# main_02.net
KiCad netlist of a schematic drawn in EAGLE
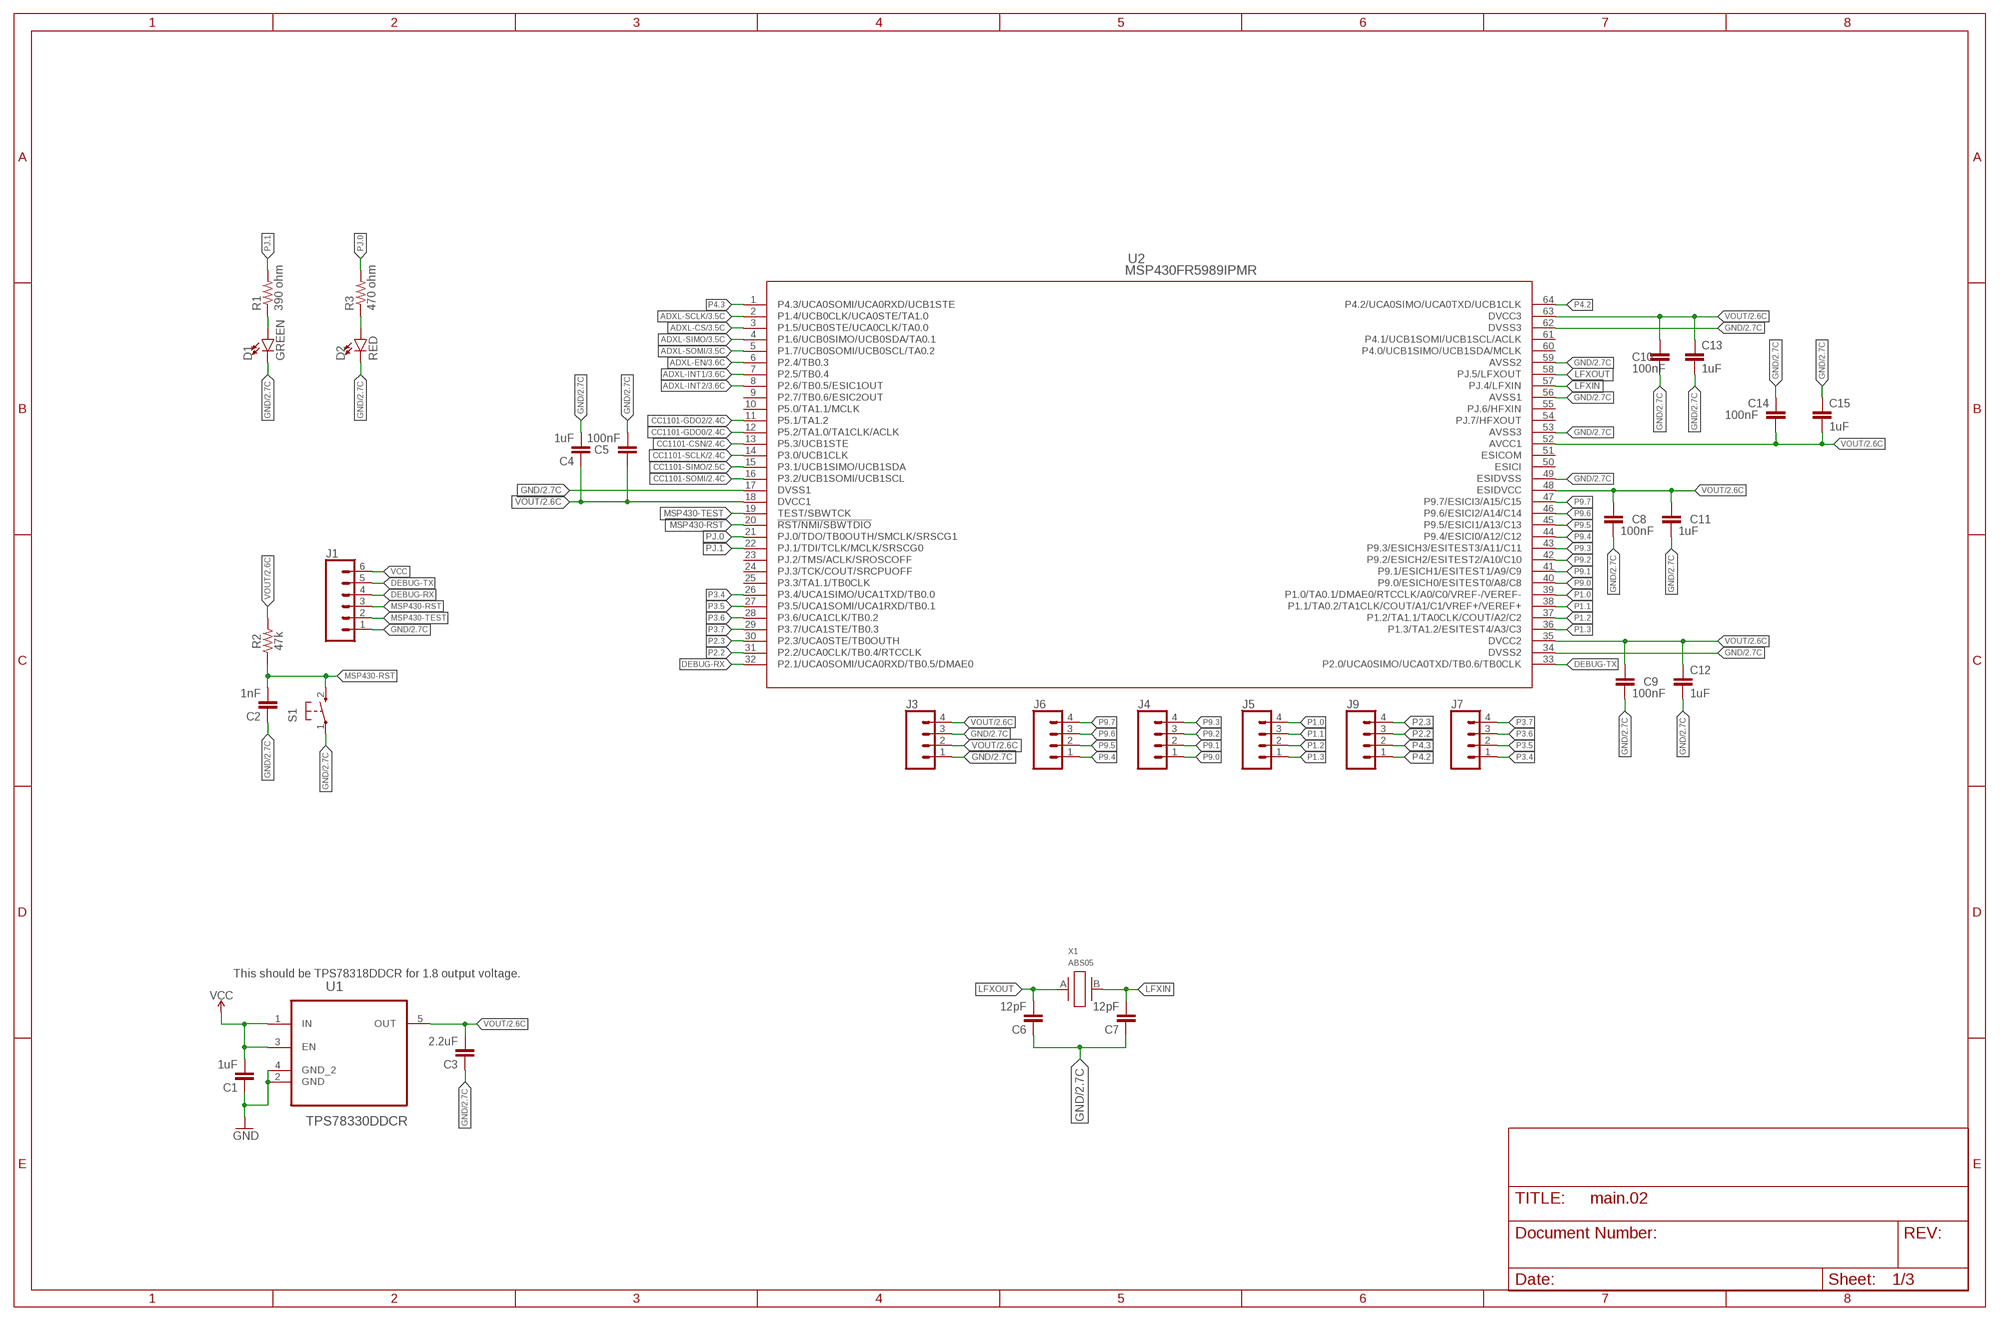
[diagram p0: schematic, sheet 1]
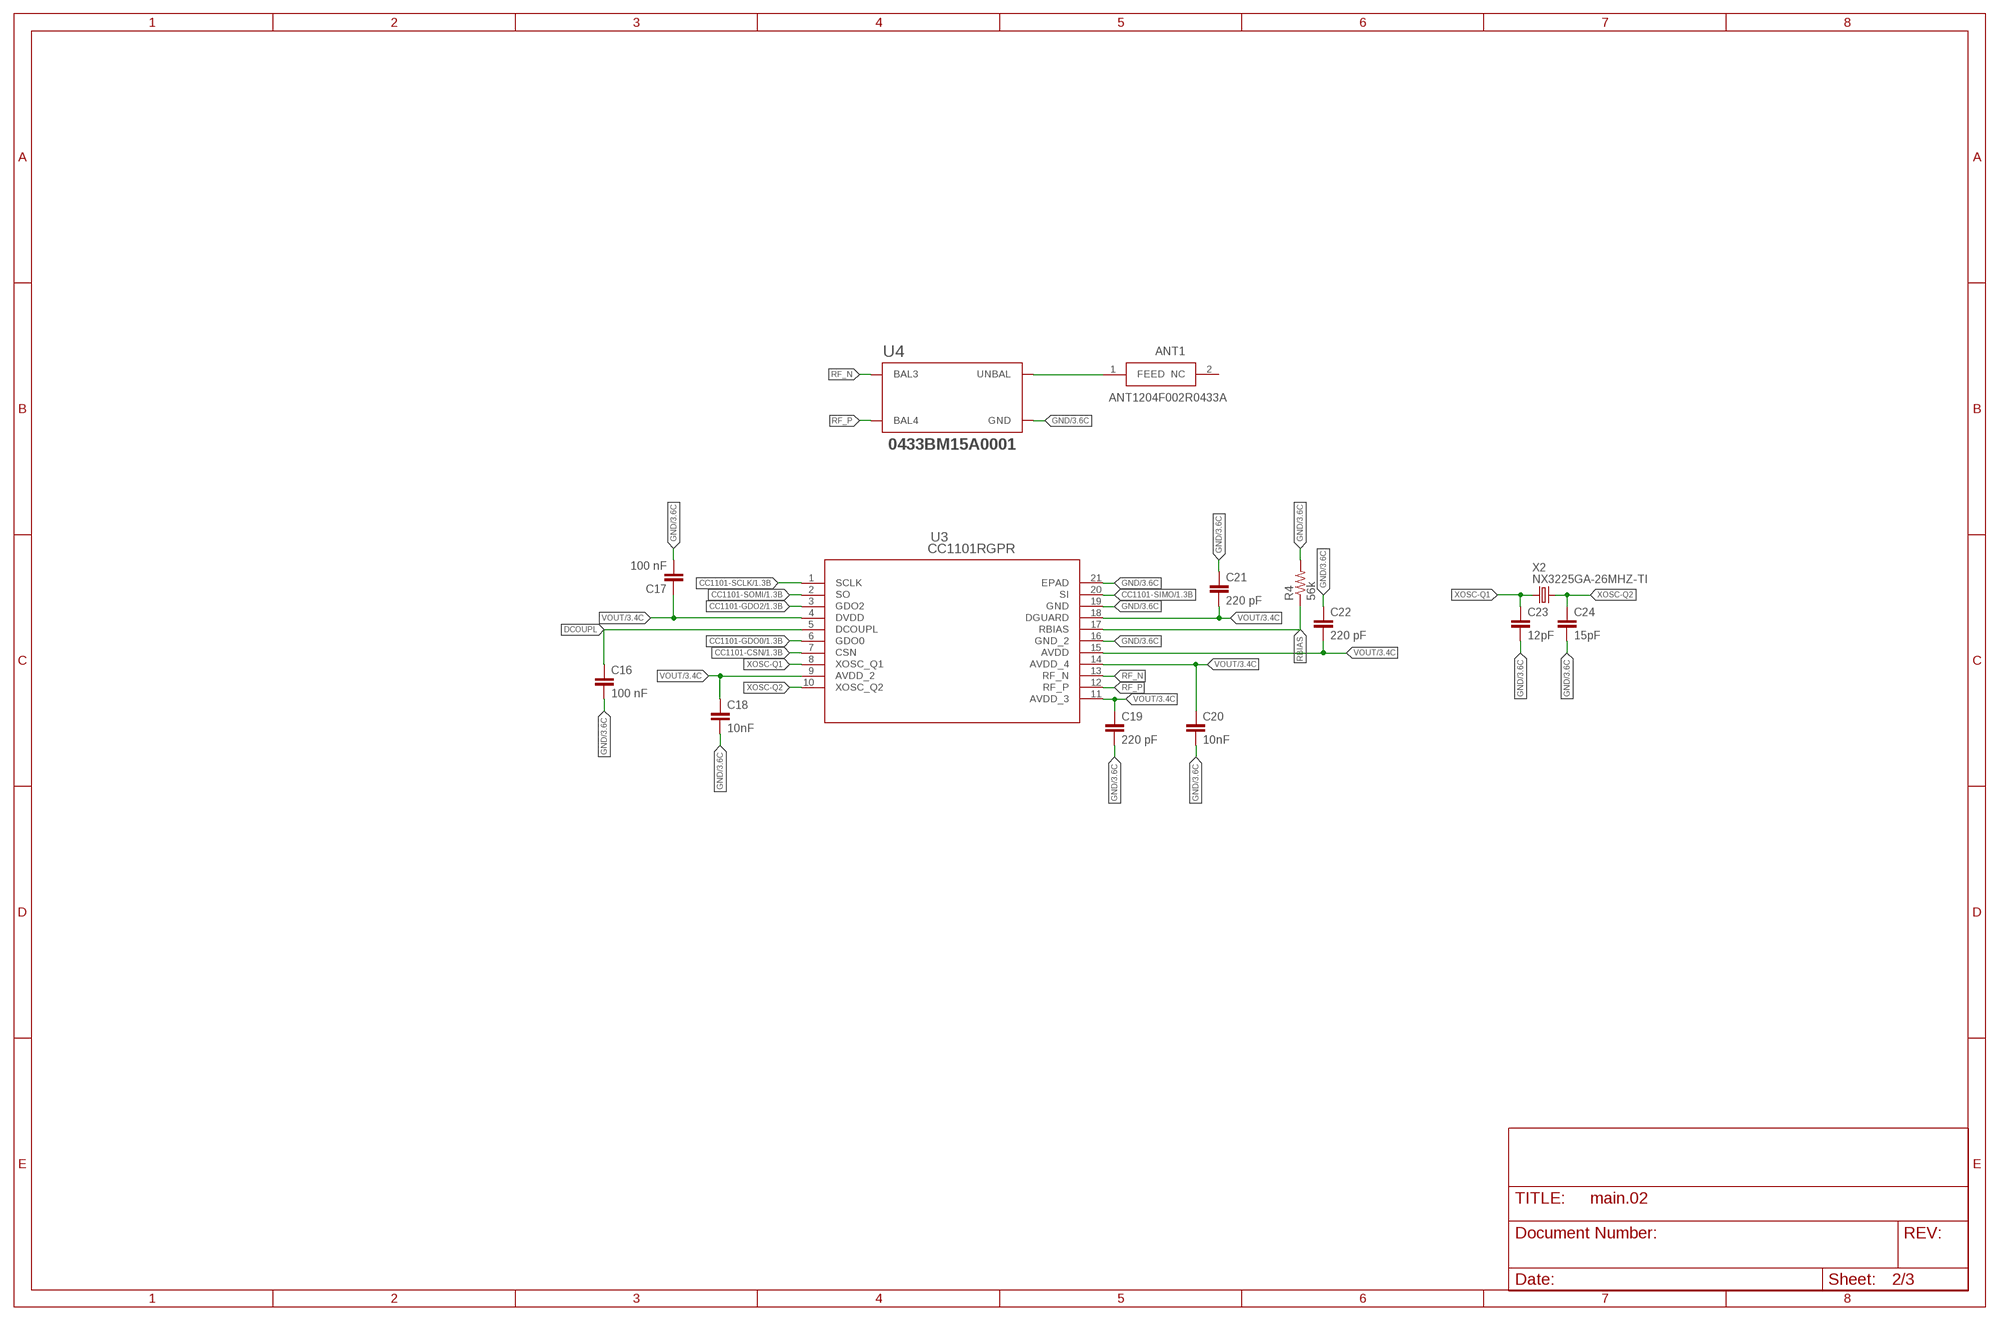
[diagram p1: schematic, sheet 2]
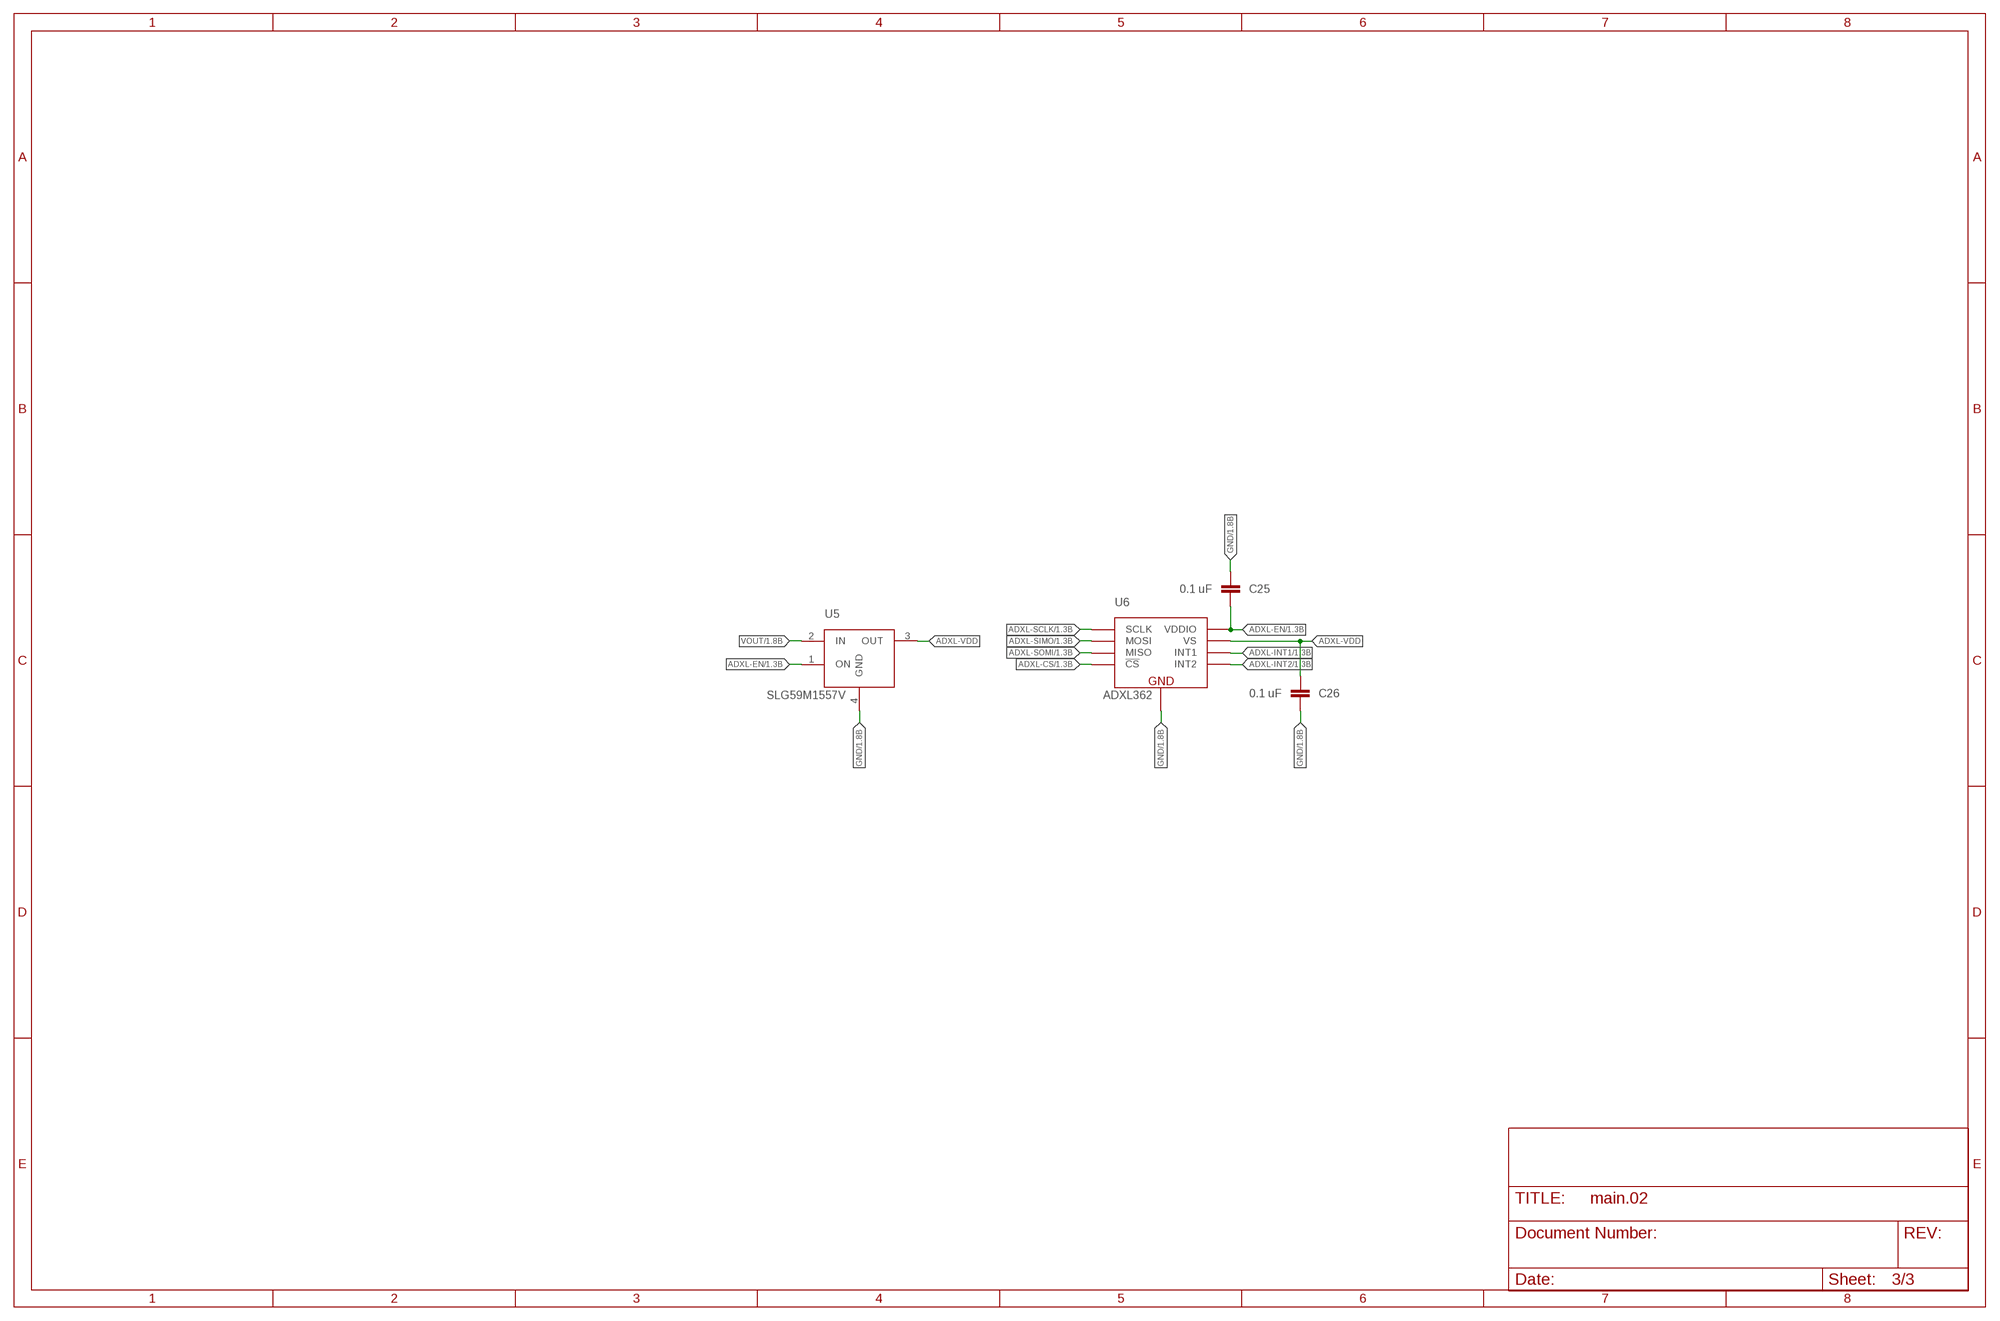
[diagram p2: schematic, sheet 3]

(export (version "E")
  (design (tool "Eeschema 10.0.6"))
  (components
    (comp (ref "ANT1")
      (value "ANT1204F002R0433A")
      (footprint "eagle-import:ANTC12340X180N")
      (fields (field (name "MOUSER_PART_NUMBER") "603-ANT1204F002R0433"))
      (libsource (lib "eagle-import") (part "ANT1204F002R0433A"))
    )
    (comp (ref "C16")
      (value "100 nF")
      (footprint "eagle-import:0603")
      (fields (field (name "MPN") "GCJ188R71H104KA12D"))
      (libsource (lib "eagle-import") (part "C-EU0603"))
    )
    (comp (ref "C17")
      (value "100 nF")
      (footprint "eagle-import:0603")
      (fields (field (name "MPN") "GCJ188R71H104KA12D"))
      (libsource (lib "eagle-import") (part "C-EU0603"))
    )
    (comp (ref "C18")
      (value "10nF")
      (footprint "eagle-import:0603")
      (fields (field (name "MPN") "GCJ188R71H104KA12D"))
      (libsource (lib "eagle-import") (part "C-EU0603"))
    )
    (comp (ref "C19")
      (value "220 pF")
      (footprint "eagle-import:0603")
      (fields (field (name "MPN") "GCJ188R71H104KA12D"))
      (libsource (lib "eagle-import") (part "C-EU0603"))
    )
    (comp (ref "C20")
      (value "10nF")
      (footprint "eagle-import:0603")
      (fields (field (name "MPN") "GCJ188R71H104KA12D"))
      (libsource (lib "eagle-import") (part "C-EU0603"))
    )
    (comp (ref "C21")
      (value "220 pF")
      (footprint "eagle-import:0603")
      (fields (field (name "MPN") "GCJ188R71H104KA12D"))
      (libsource (lib "eagle-import") (part "C-EU0603"))
    )
    (comp (ref "C22")
      (value "220 pF")
      (footprint "eagle-import:0603")
      (fields (field (name "MPN") "GCJ188R71H104KA12D"))
      (libsource (lib "eagle-import") (part "C-EU0603"))
    )
    (comp (ref "C23")
      (value "12pF")
      (footprint "eagle-import:0603")
      (fields (field (name "MPN") "06035A120FAT2A"))
      (libsource (lib "eagle-import") (part "C-EU0603"))
    )
    (comp (ref "C24")
      (value "15pF")
      (footprint "eagle-import:0603")
      (fields (field (name "MPN") "C1608C0G1H150J080AA"))
      (libsource (lib "eagle-import") (part "C-EU0603"))
    )
    (comp (ref "R4")
      (value "56k")
      (footprint "eagle-import:0603")
      (fields (field (name "MPN") "ERJ-3GEYJ563V"))
      (libsource (lib "eagle-import") (part "R-EU0603"))
    )
    (comp (ref "U3")
      (value "CC1101RGPR")
      (footprint "eagle-import:RGP20_2P4X2P4")
      (libsource (lib "eagle-import") (part "CC1101RGPR"))
    )
    (comp (ref "U4")
      (value "0433BM15A0001")
      (footprint "eagle-import:XXXXBM15A0001")
      (libsource (lib "eagle-import") (part "0433BM15A0001"))
    )
    (comp (ref "X2")
      (value "NX3225GA-26MHZ-TI")
      (footprint "eagle-import:XTAL-3.2X2.5")
      (libsource (lib "eagle-import") (part "XTAL-3.2X2.5"))
    )
    (comp (ref "C1")
      (value "1uF")
      (footprint "eagle-import:0603")
      (libsource (lib "eagle-import") (part "C-EU0603"))
    )
    (comp (ref "C2")
      (value "1nF")
      (footprint "eagle-import:0603")
      (libsource (lib "eagle-import") (part "C-EU0603"))
    )
    (comp (ref "C3")
      (value "2.2uF")
      (footprint "eagle-import:0603")
      (libsource (lib "eagle-import") (part "C-EU0603"))
    )
    (comp (ref "C4")
      (value "1uF")
      (footprint "eagle-import:0603")
      (libsource (lib "eagle-import") (part "C-EU0603"))
    )
    (comp (ref "C5")
      (value "100nF")
      (footprint "eagle-import:0603")
      (libsource (lib "eagle-import") (part "C-EU0603"))
    )
    (comp (ref "C6")
      (value "12pF")
      (footprint "eagle-import:0603")
      (fields (field (name "MPN") "CL10C120JB8NNNC"))
      (libsource (lib "eagle-import") (part "C-EU0603"))
    )
    (comp (ref "C7")
      (value "12pF")
      (footprint "eagle-import:0603")
      (fields (field (name "MPN") "CL10C120JB8NNNC"))
      (libsource (lib "eagle-import") (part "C-EU0603"))
    )
    (comp (ref "C8")
      (value "100nF")
      (footprint "eagle-import:0603")
      (libsource (lib "eagle-import") (part "C-EU0603"))
    )
    (comp (ref "C9")
      (value "100nF")
      (footprint "eagle-import:0603")
      (libsource (lib "eagle-import") (part "C-EU0603"))
    )
    (comp (ref "C10")
      (value "100nF")
      (footprint "eagle-import:0603")
      (libsource (lib "eagle-import") (part "C-EU0603"))
    )
    (comp (ref "C11")
      (value "1uF")
      (footprint "eagle-import:0603")
      (libsource (lib "eagle-import") (part "C-EU0603"))
    )
    (comp (ref "C12")
      (value "1uF")
      (footprint "eagle-import:0603")
      (libsource (lib "eagle-import") (part "C-EU0603"))
    )
    (comp (ref "C13")
      (value "1uF")
      (footprint "eagle-import:0603")
      (libsource (lib "eagle-import") (part "C-EU0603"))
    )
    (comp (ref "C14")
      (value "100nF")
      (footprint "eagle-import:0603")
      (libsource (lib "eagle-import") (part "C-EU0603"))
    )
    (comp (ref "C15")
      (value "1uF")
      (footprint "eagle-import:0603")
      (libsource (lib "eagle-import") (part "C-EU0603"))
    )
    (comp (ref "D1")
      (value "GREEN")
      (footprint "eagle-import:LED-0603")
      (libsource (lib "eagle-import") (part "LED-GREEN0603"))
    )
    (comp (ref "D2")
      (value "RED")
      (footprint "eagle-import:LED-0603")
      (libsource (lib "eagle-import") (part "LED-RED0603"))
    )
    (comp (ref "J1")
      (value "CONN_06SILK_FEMALE_PTH")
      (footprint "eagle-import:1X06")
      (libsource (lib "eagle-import") (part "CONN_06SILK_FEMALE_PTH"))
    )
    (comp (ref "J3")
      (value "CONN_041.27MM")
      (footprint "eagle-import:1X04_1.27MM")
      (fields (field (name "SPICEPREFIX") "E"))
      (libsource (lib "eagle-import") (part "CONN_041.27MM"))
    )
    (comp (ref "J4")
      (value "CONN_041.27MM")
      (footprint "eagle-import:1X04_1.27MM")
      (fields (field (name "SPICEPREFIX") "E"))
      (libsource (lib "eagle-import") (part "CONN_041.27MM"))
    )
    (comp (ref "J5")
      (value "CONN_041.27MM")
      (footprint "eagle-import:1X04_1.27MM")
      (fields (field (name "SPICEPREFIX") "E"))
      (libsource (lib "eagle-import") (part "CONN_041.27MM"))
    )
    (comp (ref "J6")
      (value "CONN_041.27MM")
      (footprint "eagle-import:1X04_1.27MM")
      (fields (field (name "SPICEPREFIX") "E"))
      (libsource (lib "eagle-import") (part "CONN_041.27MM"))
    )
    (comp (ref "J7")
      (value "CONN_041.27MM")
      (footprint "eagle-import:1X04_1.27MM")
      (fields (field (name "SPICEPREFIX") "E"))
      (libsource (lib "eagle-import") (part "CONN_041.27MM"))
    )
    (comp (ref "J9")
      (value "CONN_041.27MM")
      (footprint "eagle-import:1X04_1.27MM")
      (fields (field (name "SPICEPREFIX") "E"))
      (libsource (lib "eagle-import") (part "CONN_041.27MM"))
    )
    (comp (ref "R1")
      (value "390 ohm")
      (footprint "eagle-import:0402")
      (libsource (lib "eagle-import") (part "R-EU"))
    )
    (comp (ref "R2")
      (value "47k")
      (footprint "eagle-import:0603")
      (libsource (lib "eagle-import") (part "47KOHM-0603-1/10W-1%"))
    )
    (comp (ref "R3")
      (value "470 ohm")
      (footprint "eagle-import:0402")
      (libsource (lib "eagle-import") (part "R-EU"))
    )
    (comp (ref "S1")
      (value "ELECTRICALMETER_PB")
      (footprint "eagle-import:ELECTRICALMETER_PBTH")
      (libsource (lib "eagle-import") (part "ELECTRICALMETER_PB"))
    )
    (comp (ref "U1")
      (value "TPS78330DDCR")
      (footprint "eagle-import:SOT95P280X110-5N")
      (libsource (lib "eagle-import") (part "TPS78330DDCR"))
    )
    (comp (ref "U2")
      (value "MSP430FR5989IPMR")
      (footprint "eagle-import:PM64")
      (libsource (lib "eagle-import") (part "MSP430FR5989IPMR"))
    )
    (comp (ref "X1")
      (value "ABS05")
      (footprint "eagle-import:ABS05")
      (fields (field (name "MPN") "ABS05-32.768KHZ-9-T "))
      (libsource (lib "eagle-import") (part "ABS05-32.768KHZ-9-T"))
    )
    (comp (ref "C25")
      (value "0.1 uF")
      (footprint "eagle-import:0603")
      (libsource (lib "eagle-import") (part "C-EU0603"))
    )
    (comp (ref "C26")
      (value "0.1 uF")
      (footprint "eagle-import:0603")
      (libsource (lib "eagle-import") (part "C-EU0603"))
    )
    (comp (ref "U5")
      (value "SLG59M1557V")
      (footprint "eagle-import:4STDFN")
      (fields (field (name "MPN") "SLG59M1557V "))
      (libsource (lib "eagle-import") (part "SLG59M1557V"))
    )
    (comp (ref "U6")
      (value "ADXL362")
      (footprint "eagle-import:ADXL362")
      (fields (field (name "MPN") "ADXL362BCCZ-RL7 "))
      (libsource (lib "eagle-import") (part "ADXL362"))
    )
  )
  (nets
    (net (code "1") (name "ADXL-CS") (class "Default")
      (node (ref "U2") (pin "3") (pinfunction "P1.5/UCB0STE/UCA0CLK/TA0.0_3") (pintype "bidirectional"))
      (node (ref "U6") (pin "P$8") (pinfunction "~{CS}_P$8") (pintype "bidirectional"))
    )
    (net (code "2") (name "ADXL-EN") (class "Default")
      (node (ref "C25") (pin "1") (pinfunction "1_1") (pintype "passive"))
      (node (ref "U2") (pin "6") (pinfunction "P2.4/TB0.3_6") (pintype "bidirectional"))
      (node (ref "U5") (pin "1") (pinfunction "ON_1") (pintype "bidirectional"))
      (node (ref "U6") (pin "P$1") (pinfunction "VDDIO_P$1") (pintype "bidirectional"))
    )
    (net (code "3") (name "ADXL-INT1") (class "Default")
      (node (ref "U2") (pin "7") (pinfunction "P2.5/TB0.4_7") (pintype "bidirectional"))
      (node (ref "U6") (pin "P$11") (pinfunction "INT1_P$11") (pintype "bidirectional"))
    )
    (net (code "4") (name "ADXL-INT2") (class "Default")
      (node (ref "U2") (pin "8") (pinfunction "P2.6/TB0.5/ESIC1OUT_8") (pintype "bidirectional"))
      (node (ref "U6") (pin "P$9") (pinfunction "INT2_P$9") (pintype "bidirectional"))
    )
    (net (code "5") (name "ADXL-SCLK") (class "Default")
      (node (ref "U2") (pin "2") (pinfunction "P1.4/UCB0CLK/UCA0STE/TA1.0_2") (pintype "bidirectional"))
      (node (ref "U6") (pin "P$4") (pinfunction "SCLK_P$4") (pintype "bidirectional"))
    )
    (net (code "6") (name "ADXL-SIMO") (class "Default")
      (node (ref "U2") (pin "4") (pinfunction "P1.6/UCB0SIMO/UCB0SDA/TA0.1_4") (pintype "bidirectional"))
      (node (ref "U6") (pin "P$6") (pinfunction "MOSI_P$6") (pintype "bidirectional"))
    )
    (net (code "7") (name "ADXL-SOMI") (class "Default")
      (node (ref "U2") (pin "5") (pinfunction "P1.7/UCB0SOMI/UCB0SCL/TA0.2_5") (pintype "bidirectional"))
      (node (ref "U6") (pin "P$7") (pinfunction "MISO_P$7") (pintype "bidirectional"))
    )
    (net (code "8") (name "ADXL-VDD") (class "Default")
      (node (ref "C26") (pin "2") (pinfunction "2_2") (pintype "passive"))
      (node (ref "U5") (pin "3") (pinfunction "OUT_3") (pintype "bidirectional"))
      (node (ref "U6") (pin "P$14") (pinfunction "VS_P$14") (pintype "bidirectional"))
    )
    (net (code "9") (name "CC1101-CSN") (class "Default")
      (node (ref "U2") (pin "13") (pinfunction "P5.3/UCB1STE_13") (pintype "bidirectional"))
      (node (ref "U3") (pin "7") (pinfunction "CSN_7") (pintype "input"))
    )
    (net (code "10") (name "CC1101-GDO0") (class "Default")
      (node (ref "U2") (pin "12") (pinfunction "P5.2/TA1.0/TA1CLK/ACLK_12") (pintype "bidirectional"))
      (node (ref "U3") (pin "6") (pinfunction "GDO0_6") (pintype "bidirectional"))
    )
    (net (code "11") (name "CC1101-GDO2") (class "Default")
      (node (ref "U2") (pin "11") (pinfunction "P5.1/TA1.2_11") (pintype "bidirectional"))
      (node (ref "U3") (pin "3") (pinfunction "GDO2_3") (pintype "output"))
    )
    (net (code "12") (name "CC1101-SCLK") (class "Default")
      (node (ref "U2") (pin "14") (pinfunction "P3.0/UCB1CLK_14") (pintype "bidirectional"))
      (node (ref "U3") (pin "1") (pinfunction "SCLK_1") (pintype "passive"))
    )
    (net (code "13") (name "CC1101-SIMO") (class "Default")
      (node (ref "U2") (pin "15") (pinfunction "P3.1/UCB1SIMO/UCB1SDA_15") (pintype "bidirectional"))
      (node (ref "U3") (pin "20") (pinfunction "SI_20") (pintype "input"))
    )
    (net (code "14") (name "CC1101-SOMI") (class "Default")
      (node (ref "U2") (pin "16") (pinfunction "P3.2/UCB1SOMI/UCB1SCL_16") (pintype "bidirectional"))
      (node (ref "U3") (pin "2") (pinfunction "SO_2") (pintype "output"))
    )
    (net (code "15") (name "DCOUPL") (class "Default")
      (node (ref "C16") (pin "1") (pinfunction "1_1") (pintype "passive"))
      (node (ref "U3") (pin "5") (pinfunction "DCOUPL_5") (pintype "power_in"))
    )
    (net (code "16") (name "DEBUG-RX") (class "Default")
      (node (ref "J1") (pin "4") (pinfunction "4_4") (pintype "passive"))
      (node (ref "U2") (pin "32") (pinfunction "P2.1/UCA0SOMI/UCA0RXD/TB0.5/DMAE0_32") (pintype "bidirectional"))
    )
    (net (code "17") (name "DEBUG-TX") (class "Default")
      (node (ref "J1") (pin "5") (pinfunction "5_5") (pintype "passive"))
      (node (ref "U2") (pin "33") (pinfunction "P2.0/UCA0SIMO/UCA0TXD/TB0.6/TB0CLK_33") (pintype "bidirectional"))
    )
    (net (code "18") (name "GND") (class "Default")
      (node (ref "C1") (pin "1") (pinfunction "1_1") (pintype "passive"))
      (node (ref "C10") (pin "2") (pinfunction "2_2") (pintype "passive"))
      (node (ref "C11") (pin "2") (pinfunction "2_2") (pintype "passive"))
      (node (ref "C12") (pin "2") (pinfunction "2_2") (pintype "passive"))
      (node (ref "C13") (pin "2") (pinfunction "2_2") (pintype "passive"))
      (node (ref "C14") (pin "1") (pinfunction "1_1") (pintype "passive"))
      (node (ref "C15") (pin "1") (pinfunction "1_1") (pintype "passive"))
      (node (ref "C16") (pin "2") (pinfunction "2_2") (pintype "passive"))
      (node (ref "C17") (pin "2") (pinfunction "2_2") (pintype "passive"))
      (node (ref "C18") (pin "2") (pinfunction "2_2") (pintype "passive"))
      (node (ref "C19") (pin "2") (pinfunction "2_2") (pintype "passive"))
      (node (ref "C2") (pin "1") (pinfunction "1_1") (pintype "passive"))
      (node (ref "C20") (pin "2") (pinfunction "2_2") (pintype "passive"))
      (node (ref "C21") (pin "1") (pinfunction "1_1") (pintype "passive"))
      (node (ref "C22") (pin "1") (pinfunction "1_1") (pintype "passive"))
      (node (ref "C23") (pin "2") (pinfunction "2_2") (pintype "passive"))
      (node (ref "C24") (pin "2") (pinfunction "2_2") (pintype "passive"))
      (node (ref "C25") (pin "2") (pinfunction "2_2") (pintype "passive"))
      (node (ref "C26") (pin "1") (pinfunction "1_1") (pintype "passive"))
      (node (ref "C3") (pin "1") (pinfunction "1_1") (pintype "passive"))
      (node (ref "C4") (pin "2") (pinfunction "2_2") (pintype "passive"))
      (node (ref "C5") (pin "2") (pinfunction "2_2") (pintype "passive"))
      (node (ref "C6") (pin "1") (pinfunction "1_1") (pintype "passive"))
      (node (ref "C7") (pin "1") (pinfunction "1_1") (pintype "passive"))
      (node (ref "C8") (pin "2") (pinfunction "2_2") (pintype "passive"))
      (node (ref "C9") (pin "2") (pinfunction "2_2") (pintype "passive"))
      (node (ref "D1") (pin "C") (pinfunction "C_C") (pintype "passive"))
      (node (ref "D2") (pin "C") (pinfunction "C_C") (pintype "passive"))
      (node (ref "J1") (pin "1") (pinfunction "1_1") (pintype "passive"))
      (node (ref "J3") (pin "1") (pinfunction "1_1") (pintype "passive"))
      (node (ref "J3") (pin "3") (pinfunction "3_3") (pintype "passive"))
      (node (ref "R4") (pin "2") (pinfunction "2_2") (pintype "passive"))
      (node (ref "S1") (pin "1") (pinfunction "P_1") (pintype "passive"))
      (node (ref "U1") (pin "2") (pinfunction "GND_2") (pintype "passive"))
      (node (ref "U1") (pin "4") (pinfunction "GND_2_4") (pintype "passive"))
      (node (ref "U2") (pin "17") (pinfunction "DVSS1_17") (pintype "power_in"))
      (node (ref "U2") (pin "34") (pinfunction "DVSS2_34") (pintype "power_in"))
      (node (ref "U2") (pin "49") (pinfunction "ESIDVSS_49") (pintype "power_in"))
      (node (ref "U2") (pin "53") (pinfunction "AVSS3_53") (pintype "power_in"))
      (node (ref "U2") (pin "56") (pinfunction "AVSS1_56") (pintype "power_in"))
      (node (ref "U2") (pin "59") (pinfunction "AVSS2_59") (pintype "power_in"))
      (node (ref "U2") (pin "62") (pinfunction "DVSS3_62") (pintype "power_in"))
      (node (ref "U3") (pin "16") (pinfunction "GND_2_16") (pintype "power_in"))
      (node (ref "U3") (pin "19") (pinfunction "GND_19") (pintype "power_in"))
      (node (ref "U3") (pin "21") (pinfunction "EPAD_21") (pintype "power_in"))
      (node (ref "U4") (pin "2") (pinfunction "GND_2") (pintype "bidirectional"))
      (node (ref "U4") (pin "5") (pinfunction "GND_5") (pintype "bidirectional"))
      (node (ref "U4") (pin "6") (pinfunction "GND_6") (pintype "bidirectional"))
      (node (ref "U5") (pin "4") (pinfunction "GND_4") (pintype "bidirectional"))
      (node (ref "U6") (pin "P$12") (pinfunction "GND_P$12") (pintype "bidirectional"))
      (node (ref "U6") (pin "P$13") (pinfunction "GND_P$13") (pintype "bidirectional"))
      (node (ref "U6") (pin "P$16") (pinfunction "GND_P$16") (pintype "bidirectional"))
    )
    (net (code "19") (name "LFXIN") (class "Default")
      (node (ref "C7") (pin "2") (pinfunction "2_2") (pintype "passive"))
      (node (ref "U2") (pin "57") (pinfunction "PJ.4/LFXIN_57") (pintype "bidirectional"))
      (node (ref "X1") (pin "B") (pinfunction "2_B") (pintype "bidirectional"))
    )
    (net (code "20") (name "LFXOUT") (class "Default")
      (node (ref "C6") (pin "2") (pinfunction "2_2") (pintype "passive"))
      (node (ref "U2") (pin "58") (pinfunction "PJ.5/LFXOUT_58") (pintype "bidirectional"))
      (node (ref "X1") (pin "A") (pinfunction "1_A") (pintype "bidirectional"))
    )
    (net (code "21") (name "MSP430-RST") (class "Default")
      (node (ref "C2") (pin "2") (pinfunction "2_2") (pintype "passive"))
      (node (ref "J1") (pin "3") (pinfunction "3_3") (pintype "passive"))
      (node (ref "R2") (pin "1") (pinfunction "1_1") (pintype "passive"))
      (node (ref "S1") (pin "2") (pinfunction "S_2") (pintype "passive"))
      (node (ref "U2") (pin "20") (pinfunction "~{RST/NMI/SBWTDIO}_20") (pintype "bidirectional"))
    )
    (net (code "22") (name "MSP430-TEST") (class "Default")
      (node (ref "J1") (pin "2") (pinfunction "2_2") (pintype "passive"))
      (node (ref "U2") (pin "19") (pinfunction "TEST/SBWTCK_19") (pintype "input"))
    )
    (net (code "23") (name "Net-(ANT1-FEED)") (class "Default")
      (node (ref "ANT1") (pin "1") (pinfunction "FEED_1") (pintype "input"))
      (node (ref "U4") (pin "1") (pinfunction "UNBAL_1") (pintype "bidirectional"))
    )
    (net (code "24") (name "Net-(D1-PadA)") (class "Default")
      (node (ref "D1") (pin "A") (pinfunction "A_A") (pintype "passive"))
      (node (ref "R1") (pin "1") (pinfunction "1_1") (pintype "passive"))
    )
    (net (code "25") (name "Net-(D2-PadA)") (class "Default")
      (node (ref "D2") (pin "A") (pinfunction "A_A") (pintype "passive"))
      (node (ref "R3") (pin "1") (pinfunction "1_1") (pintype "passive"))
    )
    (net (code "26") (name "P1.0") (class "Default")
      (node (ref "J5") (pin "4") (pinfunction "4_4") (pintype "passive"))
      (node (ref "U2") (pin "39") (pinfunction "P1.0/TA0.1/DMAE0/RTCCLK/A0/C0/VREF-/VEREF-_39") (pintype "bidirectional"))
    )
    (net (code "27") (name "P1.1") (class "Default")
      (node (ref "J5") (pin "3") (pinfunction "3_3") (pintype "passive"))
      (node (ref "U2") (pin "38") (pinfunction "P1.1/TA0.2/TA1CLK/COUT/A1/C1/VREF+/VEREF+_38") (pintype "bidirectional"))
    )
    (net (code "28") (name "P1.2") (class "Default")
      (node (ref "J5") (pin "2") (pinfunction "2_2") (pintype "passive"))
      (node (ref "U2") (pin "37") (pinfunction "P1.2/TA1.1/TA0CLK/COUT/A2/C2_37") (pintype "bidirectional"))
    )
    (net (code "29") (name "P1.3") (class "Default")
      (node (ref "J5") (pin "1") (pinfunction "1_1") (pintype "passive"))
      (node (ref "U2") (pin "36") (pinfunction "P1.3/TA1.2/ESITEST4/A3/C3_36") (pintype "bidirectional"))
    )
    (net (code "30") (name "P2.2") (class "Default")
      (node (ref "J9") (pin "3") (pinfunction "3_3") (pintype "passive"))
      (node (ref "U2") (pin "31") (pinfunction "P2.2/UCA0CLK/TB0.4/RTCCLK_31") (pintype "bidirectional"))
    )
    (net (code "31") (name "P2.3") (class "Default")
      (node (ref "J9") (pin "4") (pinfunction "4_4") (pintype "passive"))
      (node (ref "U2") (pin "30") (pinfunction "P2.3/UCA0STE/TB0OUTH_30") (pintype "bidirectional"))
    )
    (net (code "32") (name "P3.4") (class "Default")
      (node (ref "J7") (pin "1") (pinfunction "1_1") (pintype "passive"))
      (node (ref "U2") (pin "26") (pinfunction "P3.4/UCA1SIMO/UCA1TXD/TB0.0_26") (pintype "bidirectional"))
    )
    (net (code "33") (name "P3.5") (class "Default")
      (node (ref "J7") (pin "2") (pinfunction "2_2") (pintype "passive"))
      (node (ref "U2") (pin "27") (pinfunction "P3.5/UCA1SOMI/UCA1RXD/TB0.1_27") (pintype "bidirectional"))
    )
    (net (code "34") (name "P3.6") (class "Default")
      (node (ref "J7") (pin "3") (pinfunction "3_3") (pintype "passive"))
      (node (ref "U2") (pin "28") (pinfunction "P3.6/UCA1CLK/TB0.2_28") (pintype "bidirectional"))
    )
    (net (code "35") (name "P3.7") (class "Default")
      (node (ref "J7") (pin "4") (pinfunction "4_4") (pintype "passive"))
      (node (ref "U2") (pin "29") (pinfunction "P3.7/UCA1STE/TB0.3_29") (pintype "bidirectional"))
    )
    (net (code "36") (name "P4.2") (class "Default")
      (node (ref "J9") (pin "1") (pinfunction "1_1") (pintype "passive"))
      (node (ref "U2") (pin "64") (pinfunction "P4.2/UCA0SIMO/UCA0TXD/UCB1CLK_64") (pintype "bidirectional"))
    )
    (net (code "37") (name "P4.3") (class "Default")
      (node (ref "J9") (pin "2") (pinfunction "2_2") (pintype "passive"))
      (node (ref "U2") (pin "1") (pinfunction "P4.3/UCA0SOMI/UCA0RXD/UCB1STE_1") (pintype "bidirectional"))
    )
    (net (code "38") (name "P9.0") (class "Default")
      (node (ref "J4") (pin "1") (pinfunction "1_1") (pintype "passive"))
      (node (ref "U2") (pin "40") (pinfunction "P9.0/ESICH0/ESITEST0/A8/C8_40") (pintype "bidirectional"))
    )
    (net (code "39") (name "P9.1") (class "Default")
      (node (ref "J4") (pin "2") (pinfunction "2_2") (pintype "passive"))
      (node (ref "U2") (pin "41") (pinfunction "P9.1/ESICH1/ESITEST1/A9/C9_41") (pintype "bidirectional"))
    )
    (net (code "40") (name "P9.2") (class "Default")
      (node (ref "J4") (pin "3") (pinfunction "3_3") (pintype "passive"))
      (node (ref "U2") (pin "42") (pinfunction "P9.2/ESICH2/ESITEST2/A10/C10_42") (pintype "bidirectional"))
    )
    (net (code "41") (name "P9.3") (class "Default")
      (node (ref "J4") (pin "4") (pinfunction "4_4") (pintype "passive"))
      (node (ref "U2") (pin "43") (pinfunction "P9.3/ESICH3/ESITEST3/A11/C11_43") (pintype "bidirectional"))
    )
    (net (code "42") (name "P9.4") (class "Default")
      (node (ref "J6") (pin "1") (pinfunction "1_1") (pintype "passive"))
      (node (ref "U2") (pin "44") (pinfunction "P9.4/ESICI0/A12/C12_44") (pintype "bidirectional"))
    )
    (net (code "43") (name "P9.5") (class "Default")
      (node (ref "J6") (pin "2") (pinfunction "2_2") (pintype "passive"))
      (node (ref "U2") (pin "45") (pinfunction "P9.5/ESICI1/A13/C13_45") (pintype "bidirectional"))
    )
    (net (code "44") (name "P9.6") (class "Default")
      (node (ref "J6") (pin "3") (pinfunction "3_3") (pintype "passive"))
      (node (ref "U2") (pin "46") (pinfunction "P9.6/ESICI2/A14/C14_46") (pintype "bidirectional"))
    )
    (net (code "45") (name "P9.7") (class "Default")
      (node (ref "J6") (pin "4") (pinfunction "4_4") (pintype "passive"))
      (node (ref "U2") (pin "47") (pinfunction "P9.7/ESICI3/A15/C15_47") (pintype "bidirectional"))
    )
    (net (code "46") (name "PJ.0") (class "Default")
      (node (ref "R3") (pin "2") (pinfunction "2_2") (pintype "passive"))
      (node (ref "U2") (pin "21") (pinfunction "PJ.0/TDO/TB0OUTH/SMCLK/SRSCG1_21") (pintype "bidirectional"))
    )
    (net (code "47") (name "PJ.1") (class "Default")
      (node (ref "R1") (pin "2") (pinfunction "2_2") (pintype "passive"))
      (node (ref "U2") (pin "22") (pinfunction "PJ.1/TDI/TCLK/MCLK/SRSCG0_22") (pintype "bidirectional"))
    )
    (net (code "48") (name "RBIAS") (class "Default")
      (node (ref "R4") (pin "1") (pinfunction "1_1") (pintype "passive"))
      (node (ref "U3") (pin "17") (pinfunction "RBIAS_17") (pintype "bidirectional"))
    )
    (net (code "49") (name "RF_N") (class "Default")
      (node (ref "U3") (pin "13") (pinfunction "RF_N_13") (pintype "bidirectional"))
      (node (ref "U4") (pin "3") (pinfunction "BAL3_3") (pintype "bidirectional"))
    )
    (net (code "50") (name "RF_P") (class "Default")
      (node (ref "U3") (pin "12") (pinfunction "RF_P_12") (pintype "bidirectional"))
      (node (ref "U4") (pin "4") (pinfunction "BAL4_4") (pintype "bidirectional"))
    )
    (net (code "51") (name "VCC") (class "Default")
      (node (ref "C1") (pin "2") (pinfunction "2_2") (pintype "passive"))
      (node (ref "J1") (pin "6") (pinfunction "6_6") (pintype "passive"))
      (node (ref "U1") (pin "1") (pinfunction "IN_1") (pintype "input"))
      (node (ref "U1") (pin "3") (pinfunction "EN_3") (pintype "input"))
    )
    (net (code "52") (name "VOUT") (class "Default")
      (node (ref "C10") (pin "1") (pinfunction "1_1") (pintype "passive"))
      (node (ref "C11") (pin "1") (pinfunction "1_1") (pintype "passive"))
      (node (ref "C12") (pin "1") (pinfunction "1_1") (pintype "passive"))
      (node (ref "C13") (pin "1") (pinfunction "1_1") (pintype "passive"))
      (node (ref "C14") (pin "2") (pinfunction "2_2") (pintype "passive"))
      (node (ref "C15") (pin "2") (pinfunction "2_2") (pintype "passive"))
      (node (ref "C17") (pin "1") (pinfunction "1_1") (pintype "passive"))
      (node (ref "C18") (pin "1") (pinfunction "1_1") (pintype "passive"))
      (node (ref "C19") (pin "1") (pinfunction "1_1") (pintype "passive"))
      (node (ref "C20") (pin "1") (pinfunction "1_1") (pintype "passive"))
      (node (ref "C21") (pin "2") (pinfunction "2_2") (pintype "passive"))
      (node (ref "C22") (pin "2") (pinfunction "2_2") (pintype "passive"))
      (node (ref "C3") (pin "2") (pinfunction "2_2") (pintype "passive"))
      (node (ref "C4") (pin "1") (pinfunction "1_1") (pintype "passive"))
      (node (ref "C5") (pin "1") (pinfunction "1_1") (pintype "passive"))
      (node (ref "C8") (pin "1") (pinfunction "1_1") (pintype "passive"))
      (node (ref "C9") (pin "1") (pinfunction "1_1") (pintype "passive"))
      (node (ref "J3") (pin "2") (pinfunction "2_2") (pintype "passive"))
      (node (ref "J3") (pin "4") (pinfunction "4_4") (pintype "passive"))
      (node (ref "R2") (pin "2") (pinfunction "2_2") (pintype "passive"))
      (node (ref "U1") (pin "5") (pinfunction "OUT_5") (pintype "output"))
      (node (ref "U2") (pin "18") (pinfunction "DVCC1_18") (pintype "power_in"))
      (node (ref "U2") (pin "35") (pinfunction "DVCC2_35") (pintype "power_in"))
      (node (ref "U2") (pin "48") (pinfunction "ESIDVCC_48") (pintype "power_in"))
      (node (ref "U2") (pin "52") (pinfunction "AVCC1_52") (pintype "power_in"))
      (node (ref "U2") (pin "63") (pinfunction "DVCC3_63") (pintype "power_in"))
      (node (ref "U3") (pin "11") (pinfunction "AVDD_3_11") (pintype "power_in"))
      (node (ref "U3") (pin "14") (pinfunction "AVDD_4_14") (pintype "power_in"))
      (node (ref "U3") (pin "15") (pinfunction "AVDD_15") (pintype "power_in"))
      (node (ref "U3") (pin "18") (pinfunction "DGUARD_18") (pintype "power_in"))
      (node (ref "U3") (pin "4") (pinfunction "DVDD_4") (pintype "power_in"))
      (node (ref "U3") (pin "9") (pinfunction "AVDD_2_9") (pintype "power_in"))
      (node (ref "U5") (pin "2") (pinfunction "IN_2") (pintype "bidirectional"))
    )
    (net (code "53") (name "XOSC-Q1") (class "Default")
      (node (ref "C23") (pin "1") (pinfunction "1_1") (pintype "passive"))
      (node (ref "U3") (pin "8") (pinfunction "XOSC_Q1_8") (pintype "bidirectional"))
      (node (ref "X2") (pin "1") (pinfunction "1_1") (pintype "passive"))
    )
    (net (code "54") (name "XOSC-Q2") (class "Default")
      (node (ref "C24") (pin "1") (pinfunction "1_1") (pintype "passive"))
      (node (ref "U3") (pin "10") (pinfunction "XOSC_Q2_10") (pintype "bidirectional"))
      (node (ref "X2") (pin "3") (pinfunction "2_3") (pintype "passive"))
    )
    (net (code "55") (name "unconnected-(ANT1-NC-Pad2)") (class "Default")
      (node (ref "ANT1") (pin "2") (pinfunction "NC_2") (pintype "no_connect"))
    )
    (net (code "56") (name "unconnected-(U2-ESICI-Pad50)") (class "Default")
      (node (ref "U2") (pin "50") (pinfunction "ESICI_50") (pintype "input"))
    )
    (net (code "57") (name "unconnected-(U2-ESICOM-Pad51)") (class "Default")
      (node (ref "U2") (pin "51") (pinfunction "ESICOM_51") (pintype "passive"))
    )
    (net (code "58") (name "unconnected-(U2-P2.7{slash}TB0.6{slash}ESIC2OUT-Pad9)") (class "Default")
      (node (ref "U2") (pin "9") (pinfunction "P2.7/TB0.6/ESIC2OUT_9") (pintype "bidirectional"))
    )
    (net (code "59") (name "unconnected-(U2-P3.3{slash}TA1.1{slash}TB0CLK-Pad25)") (class "Default")
      (node (ref "U2") (pin "25") (pinfunction "P3.3/TA1.1/TB0CLK_25") (pintype "bidirectional"))
    )
    (net (code "60") (name "unconnected-(U2-P4.0{slash}UCB1SIMO{slash}UCB1SDA{slash}MCLK-Pad60)") (class "Default")
      (node (ref "U2") (pin "60") (pinfunction "P4.0/UCB1SIMO/UCB1SDA/MCLK_60") (pintype "bidirectional"))
    )
    (net (code "61") (name "unconnected-(U2-P4.1{slash}UCB1SOMI{slash}UCB1SCL{slash}ACLK-Pad61)") (class "Default")
      (node (ref "U2") (pin "61") (pinfunction "P4.1/UCB1SOMI/UCB1SCL/ACLK_61") (pintype "bidirectional"))
    )
    (net (code "62") (name "unconnected-(U2-P5.0{slash}TA1.1{slash}MCLK-Pad10)") (class "Default")
      (node (ref "U2") (pin "10") (pinfunction "P5.0/TA1.1/MCLK_10") (pintype "bidirectional"))
    )
    (net (code "63") (name "unconnected-(U2-PJ.2{slash}TMS{slash}ACLK{slash}SROSCOFF-Pad23)") (class "Default")
      (node (ref "U2") (pin "23") (pinfunction "PJ.2/TMS/ACLK/SROSCOFF_23") (pintype "bidirectional"))
    )
    (net (code "64") (name "unconnected-(U2-PJ.3{slash}TCK{slash}COUT{slash}SRCPUOFF-Pad24)") (class "Default")
      (node (ref "U2") (pin "24") (pinfunction "PJ.3/TCK/COUT/SRCPUOFF_24") (pintype "bidirectional"))
    )
    (net (code "65") (name "unconnected-(U2-PJ.6{slash}HFXIN-Pad55)") (class "Default")
      (node (ref "U2") (pin "55") (pinfunction "PJ.6/HFXIN_55") (pintype "bidirectional"))
    )
    (net (code "66") (name "unconnected-(U2-PJ.7{slash}HFXOUT-Pad54)") (class "Default")
      (node (ref "U2") (pin "54") (pinfunction "PJ.7/HFXOUT_54") (pintype "bidirectional"))
    )
  )
)
